# Sheet1.net
KiCad netlist of a schematic drawn in Altium Designer
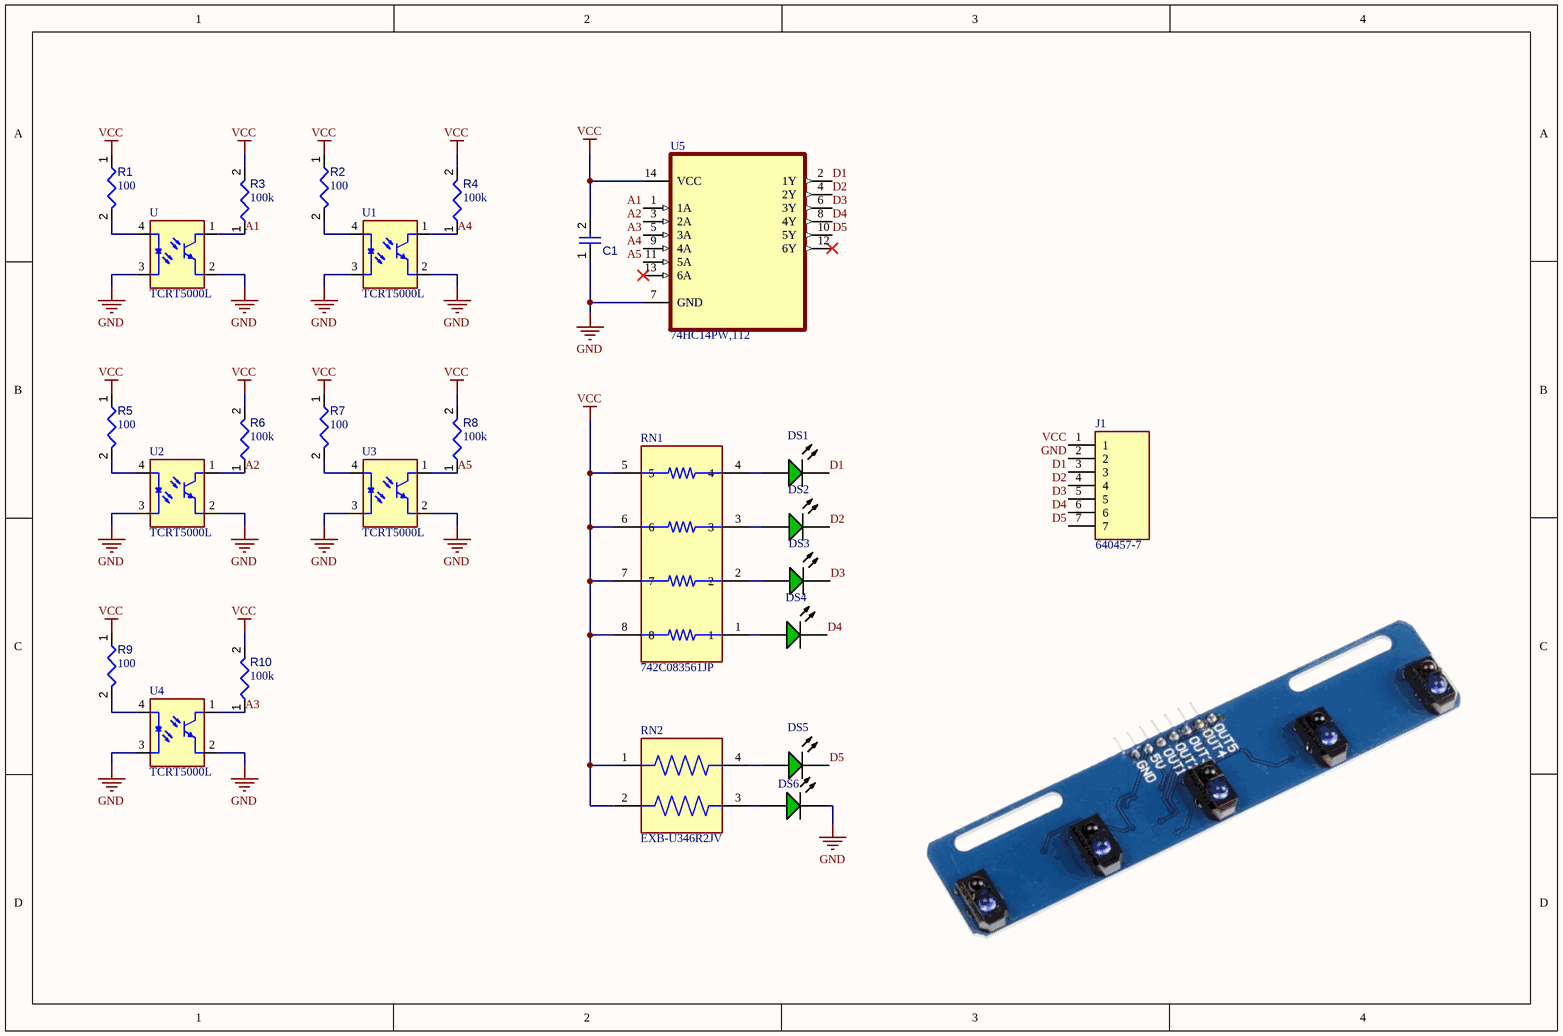
[diagram p0: Sheet1.SchDoc]

(export (version "E")
  (design (tool "Eeschema 10.0.6"))
  (components
    (comp (ref "C1")
      (value "Capacitor 1 uF +/- 10% 25 V 0805")
      (footprint "CAPC2013X145X50ML20T25")
      (description "Chip Capacitor, 1 uF, +/-10%, 25 V, 0805 (2012 Metric)")
      (fields (field (name "TOLERANCE") "10%"))
      (libsource (lib "Med khalil khlifi") (part "CAP-NP-2"))
    )
    (comp (ref "DS1")
      (value "HSMG-C190")
      (footprint "AVAG-HSMX-C190_V")
      (description "LED Uni-Color Green, 52 mW, 20 mA, -40 to 85 degC, 2-Pin SMD, RoHS, Tape and Reel")
      (fields (field (name "POWER") "52mW") (field (name "MANUFACTURER") "Avago"))
      (libsource (lib "Med khalil khlifi") (part "LED-GREEN-AK-2"))
    )
    (comp (ref "DS2")
      (value "HSMG-C190")
      (footprint "AVAG-HSMX-C190_V")
      (description "LED Uni-Color Green, 52 mW, 20 mA, -40 to 85 degC, 2-Pin SMD, RoHS, Tape and Reel")
      (fields (field (name "POWER") "52mW") (field (name "MANUFACTURER") "Avago"))
      (libsource (lib "Med khalil khlifi") (part "LED-GREEN-AK-2"))
    )
    (comp (ref "DS3")
      (value "HSMG-C190")
      (footprint "AVAG-HSMX-C190_V")
      (description "LED Uni-Color Green, 52 mW, 20 mA, -40 to 85 degC, 2-Pin SMD, RoHS, Tape and Reel")
      (fields (field (name "POWER") "52mW") (field (name "MANUFACTURER") "Avago"))
      (libsource (lib "Med khalil khlifi") (part "LED-GREEN-AK-2"))
    )
    (comp (ref "DS4")
      (value "HSMG-C190")
      (footprint "AVAG-HSMX-C190_V")
      (description "LED Uni-Color Green, 52 mW, 20 mA, -40 to 85 degC, 2-Pin SMD, RoHS, Tape and Reel")
      (fields (field (name "POWER") "52mW") (field (name "MANUFACTURER") "Avago"))
      (libsource (lib "Med khalil khlifi") (part "LED-GREEN-AK-2"))
    )
    (comp (ref "DS5")
      (value "HSMG-C190")
      (footprint "AVAG-HSMX-C190_V")
      (description "LED Uni-Color Green, 52 mW, 20 mA, -40 to 85 degC, 2-Pin SMD, RoHS, Tape and Reel")
      (fields (field (name "POWER") "52mW") (field (name "MANUFACTURER") "Avago"))
      (libsource (lib "Med khalil khlifi") (part "LED-GREEN-AK-2"))
    )
    (comp (ref "DS6")
      (value "HSMG-C190")
      (footprint "AVAG-HSMX-C190_V")
      (description "LED Uni-Color Green, 52 mW, 20 mA, -40 to 85 degC, 2-Pin SMD, RoHS, Tape and Reel")
      (fields (field (name "POWER") "52mW") (field (name "MANUFACTURER") "Avago"))
      (libsource (lib "Med khalil khlifi") (part "LED-GREEN-AK-2"))
    )
    (comp (ref "J1")
      (value "640457-7")
      (footprint "TE_640457-7")
      (description "07P MTA100 HDR ASSY SQ R/A F/L")
      (fields (field (name "MF") "TE Connectivity"))
      (libsource (lib "Header 7") (part "640457-7"))
    )
    (comp (ref "R1")
      (value "100")
      (footprint "RESC0402(1005)_L")
      (description "Chip Resistor, 100 Ohms, +/-1 %, 63 mW, -55 to 155 degC, 0402")
      (fields (field (name "POWER") "63mW") (field (name "TOLERANCE") "1%"))
      (libsource (lib "Med khalil khlifi") (part "RES-2"))
    )
    (comp (ref "R2")
      (value "100")
      (footprint "RESC0402(1005)_L")
      (description "Chip Resistor, 100 Ohms, +/-1 %, 63 mW, -55 to 155 degC, 0402")
      (fields (field (name "POWER") "63mW") (field (name "TOLERANCE") "1%"))
      (libsource (lib "Med khalil khlifi") (part "RES-2"))
    )
    (comp (ref "R3")
      (value "100k")
      (footprint "RESC1005X40X25ML05T05")
      (description "Chip Resistor, 100 KOhm, +/- 1%, 0.063 W, -55 to 155 degC, 0402 (1005 Metric)")
      (fields (field (name "TOLERANCE") "1%") (field (name "POWER") "63mW"))
      (libsource (lib "Med khalil khlifi") (part "RES-2"))
    )
    (comp (ref "R4")
      (value "100k")
      (footprint "RESC1005X40X25ML05T05")
      (description "Chip Resistor, 100 KOhm, +/- 1%, 0.063 W, -55 to 155 degC, 0402 (1005 Metric)")
      (fields (field (name "TOLERANCE") "1%") (field (name "POWER") "63mW"))
      (libsource (lib "Med khalil khlifi") (part "RES-2"))
    )
    (comp (ref "R5")
      (value "100")
      (footprint "RESC0402(1005)_L")
      (description "Chip Resistor, 100 Ohms, +/-1 %, 63 mW, -55 to 155 degC, 0402")
      (fields (field (name "POWER") "63mW") (field (name "TOLERANCE") "1%"))
      (libsource (lib "Med khalil khlifi") (part "RES-2"))
    )
    (comp (ref "R6")
      (value "100k")
      (footprint "RESC1005X40X25ML05T05")
      (description "Chip Resistor, 100 KOhm, +/- 1%, 0.063 W, -55 to 155 degC, 0402 (1005 Metric)")
      (fields (field (name "TOLERANCE") "1%") (field (name "POWER") "63mW"))
      (libsource (lib "Med khalil khlifi") (part "RES-2"))
    )
    (comp (ref "R7")
      (value "100")
      (footprint "RESC0402(1005)_L")
      (description "Chip Resistor, 100 Ohms, +/-1 %, 63 mW, -55 to 155 degC, 0402")
      (fields (field (name "POWER") "63mW") (field (name "TOLERANCE") "1%"))
      (libsource (lib "Med khalil khlifi") (part "RES-2"))
    )
    (comp (ref "R8")
      (value "100k")
      (footprint "RESC1005X40X25ML05T05")
      (description "Chip Resistor, 100 KOhm, +/- 1%, 0.063 W, -55 to 155 degC, 0402 (1005 Metric)")
      (fields (field (name "TOLERANCE") "1%") (field (name "POWER") "63mW"))
      (libsource (lib "Med khalil khlifi") (part "RES-2"))
    )
    (comp (ref "R9")
      (value "100")
      (footprint "RESC0402(1005)_L")
      (description "Chip Resistor, 100 Ohms, +/-1 %, 63 mW, -55 to 155 degC, 0402")
      (fields (field (name "POWER") "63mW") (field (name "TOLERANCE") "1%"))
      (libsource (lib "Med khalil khlifi") (part "RES-2"))
    )
    (comp (ref "R10")
      (value "100k")
      (footprint "RESC1005X40X25ML05T05")
      (description "Chip Resistor, 100 KOhm, +/- 1%, 0.063 W, -55 to 155 degC, 0402 (1005 Metric)")
      (fields (field (name "TOLERANCE") "1%") (field (name "POWER") "63mW"))
      (libsource (lib "Med khalil khlifi") (part "RES-2"))
    )
    (comp (ref "RN1")
      (value "742C083561JP")
      (footprint "RESCAV80P320X160X70-8N")
      (fields (field (name "MF") "CTS Resistor"))
      (libsource (lib "Resistor Array 4") (part "742C083561JP"))
    )
    (comp (ref "RN2")
      (value "EXB-U346R2JV")
      (footprint "RESCAXE_EXB-U346R2JV")
      (fields (field (name "MF") "Panasonic"))
      (libsource (lib "Res Array 2") (part "EXB-U346R2JV"))
    )
    (comp (ref "U")
      (value "TCRT5000L")
      (footprint "XDCR_TCRT5000L")
      (description "Reflective Optical Sensor 0.591 _15mm_ PCB Mount")
      (fields (field (name "MF") "Vishay"))
      (libsource (lib "TCRT5000L") (part "TCRT5000L"))
    )
    (comp (ref "U1")
      (value "TCRT5000L")
      (footprint "XDCR_TCRT5000L")
      (description "Reflective Optical Sensor 0.591 _15mm_ PCB Mount")
      (fields (field (name "MF") "Vishay"))
      (libsource (lib "TCRT5000L") (part "TCRT5000L"))
    )
    (comp (ref "U2")
      (value "TCRT5000L")
      (footprint "XDCR_TCRT5000L")
      (description "Reflective Optical Sensor 0.591 _15mm_ PCB Mount")
      (fields (field (name "MF") "Vishay"))
      (libsource (lib "TCRT5000L") (part "TCRT5000L"))
    )
    (comp (ref "U3")
      (value "TCRT5000L")
      (footprint "XDCR_TCRT5000L")
      (description "Reflective Optical Sensor 0.591 _15mm_ PCB Mount")
      (fields (field (name "MF") "Vishay"))
      (libsource (lib "TCRT5000L") (part "TCRT5000L"))
    )
    (comp (ref "U4")
      (value "TCRT5000L")
      (footprint "XDCR_TCRT5000L")
      (description "Reflective Optical Sensor 0.591 _15mm_ PCB Mount")
      (fields (field (name "MF") "Vishay"))
      (libsource (lib "TCRT5000L") (part "TCRT5000L"))
    )
    (comp (ref "U5")
      (value "74HC14PW,112")
      (footprint "SOP65P640X110-14N")
      (description "Inverter IC 6 Channel Schmitt Trigger 14-TSSOP")
      (fields (field (name "MF") "Nexperia"))
      (libsource (lib "74HC14") (part "74HC14PW,112"))
    )
  )
  (nets
    (net (code "1") (name "/A1") (class "Default")
      (node (ref "R3") (pin "1") (pinfunction "1_1") (pintype "passive"))
      (node (ref "U") (pin "1") (pinfunction "CO_1") (pintype "passive"))
      (node (ref "U5") (pin "1") (pinfunction "1A_1") (pintype "input"))
    )
    (net (code "2") (name "/A2") (class "Default")
      (node (ref "R6") (pin "1") (pinfunction "1_1") (pintype "passive"))
      (node (ref "U2") (pin "1") (pinfunction "CO_1") (pintype "passive"))
      (node (ref "U5") (pin "3") (pinfunction "2A_3") (pintype "input"))
    )
    (net (code "3") (name "/A3") (class "Default")
      (node (ref "R10") (pin "1") (pinfunction "1_1") (pintype "passive"))
      (node (ref "U4") (pin "1") (pinfunction "CO_1") (pintype "passive"))
      (node (ref "U5") (pin "5") (pinfunction "3A_5") (pintype "input"))
    )
    (net (code "4") (name "/A4") (class "Default")
      (node (ref "R4") (pin "1") (pinfunction "1_1") (pintype "passive"))
      (node (ref "U1") (pin "1") (pinfunction "CO_1") (pintype "passive"))
      (node (ref "U5") (pin "9") (pinfunction "4A_9") (pintype "input"))
    )
    (net (code "5") (name "/A5") (class "Default")
      (node (ref "R8") (pin "1") (pinfunction "1_1") (pintype "passive"))
      (node (ref "U3") (pin "1") (pinfunction "CO_1") (pintype "passive"))
      (node (ref "U5") (pin "11") (pinfunction "5A_11") (pintype "input"))
    )
    (net (code "6") (name "/D1") (class "Default")
      (node (ref "DS1") (pin "2") (pinfunction "K_2") (pintype "passive"))
      (node (ref "J1") (pin "3") (pinfunction "3_3") (pintype "passive"))
      (node (ref "U5") (pin "2") (pinfunction "1Y_2") (pintype "output"))
    )
    (net (code "7") (name "/D2") (class "Default")
      (node (ref "DS2") (pin "2") (pinfunction "K_2") (pintype "passive"))
      (node (ref "J1") (pin "4") (pinfunction "4_4") (pintype "passive"))
      (node (ref "U5") (pin "4") (pinfunction "2Y_4") (pintype "output"))
    )
    (net (code "8") (name "/D3") (class "Default")
      (node (ref "DS3") (pin "2") (pinfunction "K_2") (pintype "passive"))
      (node (ref "J1") (pin "5") (pinfunction "5_5") (pintype "passive"))
      (node (ref "U5") (pin "6") (pinfunction "3Y_6") (pintype "output"))
    )
    (net (code "9") (name "/D4") (class "Default")
      (node (ref "DS4") (pin "2") (pinfunction "K_2") (pintype "passive"))
      (node (ref "J1") (pin "6") (pinfunction "6_6") (pintype "passive"))
      (node (ref "U5") (pin "8") (pinfunction "4Y_8") (pintype "output"))
    )
    (net (code "10") (name "/D5") (class "Default")
      (node (ref "DS5") (pin "2") (pinfunction "K_2") (pintype "passive"))
      (node (ref "J1") (pin "7") (pinfunction "7_7") (pintype "passive"))
      (node (ref "U5") (pin "10") (pinfunction "5Y_10") (pintype "output"))
    )
    (net (code "11") (name "GND") (class "Default")
      (node (ref "C1") (pin "1") (pinfunction "1_1") (pintype "passive"))
      (node (ref "DS6") (pin "2") (pinfunction "K_2") (pintype "passive"))
      (node (ref "J1") (pin "2") (pinfunction "2_2") (pintype "passive"))
      (node (ref "U") (pin "2") (pinfunction "E_2") (pintype "passive"))
      (node (ref "U") (pin "3") (pinfunction "C_3") (pintype "passive"))
      (node (ref "U1") (pin "2") (pinfunction "E_2") (pintype "passive"))
      (node (ref "U1") (pin "3") (pinfunction "C_3") (pintype "passive"))
      (node (ref "U2") (pin "2") (pinfunction "E_2") (pintype "passive"))
      (node (ref "U2") (pin "3") (pinfunction "C_3") (pintype "passive"))
      (node (ref "U3") (pin "2") (pinfunction "E_2") (pintype "passive"))
      (node (ref "U3") (pin "3") (pinfunction "C_3") (pintype "passive"))
      (node (ref "U4") (pin "2") (pinfunction "E_2") (pintype "passive"))
      (node (ref "U4") (pin "3") (pinfunction "C_3") (pintype "passive"))
      (node (ref "U5") (pin "7") (pinfunction "GND_7") (pintype "passive"))
    )
    (net (code "12") (name "Net-(DS1-A)") (class "Default")
      (node (ref "DS1") (pin "1") (pinfunction "A_1") (pintype "passive"))
      (node (ref "RN1") (pin "4") (pinfunction "4_4") (pintype "passive"))
    )
    (net (code "13") (name "Net-(DS2-A)") (class "Default")
      (node (ref "DS2") (pin "1") (pinfunction "A_1") (pintype "passive"))
      (node (ref "RN1") (pin "3") (pinfunction "3_3") (pintype "passive"))
    )
    (net (code "14") (name "Net-(DS3-A)") (class "Default")
      (node (ref "DS3") (pin "1") (pinfunction "A_1") (pintype "passive"))
      (node (ref "RN1") (pin "2") (pinfunction "2_2") (pintype "passive"))
    )
    (net (code "15") (name "Net-(DS4-A)") (class "Default")
      (node (ref "DS4") (pin "1") (pinfunction "A_1") (pintype "passive"))
      (node (ref "RN1") (pin "1") (pinfunction "1_1") (pintype "passive"))
    )
    (net (code "16") (name "Net-(DS5-A)") (class "Default")
      (node (ref "DS5") (pin "1") (pinfunction "A_1") (pintype "passive"))
      (node (ref "RN2") (pin "4") (pinfunction "4_4") (pintype "passive"))
    )
    (net (code "17") (name "Net-(DS6-A)") (class "Default")
      (node (ref "DS6") (pin "1") (pinfunction "A_1") (pintype "passive"))
      (node (ref "RN2") (pin "3") (pinfunction "3_3") (pintype "passive"))
    )
    (net (code "18") (name "Net-(U-A)") (class "Default")
      (node (ref "R1") (pin "2") (pinfunction "2_2") (pintype "passive"))
      (node (ref "U") (pin "4") (pinfunction "A_4") (pintype "passive"))
    )
    (net (code "19") (name "Net-(U1-A)") (class "Default")
      (node (ref "R2") (pin "2") (pinfunction "2_2") (pintype "passive"))
      (node (ref "U1") (pin "4") (pinfunction "A_4") (pintype "passive"))
    )
    (net (code "20") (name "Net-(U2-A)") (class "Default")
      (node (ref "R5") (pin "2") (pinfunction "2_2") (pintype "passive"))
      (node (ref "U2") (pin "4") (pinfunction "A_4") (pintype "passive"))
    )
    (net (code "21") (name "Net-(U3-A)") (class "Default")
      (node (ref "R7") (pin "2") (pinfunction "2_2") (pintype "passive"))
      (node (ref "U3") (pin "4") (pinfunction "A_4") (pintype "passive"))
    )
    (net (code "22") (name "Net-(U4-A)") (class "Default")
      (node (ref "R9") (pin "2") (pinfunction "2_2") (pintype "passive"))
      (node (ref "U4") (pin "4") (pinfunction "A_4") (pintype "passive"))
    )
    (net (code "23") (name "VCC") (class "Default")
      (node (ref "C1") (pin "2") (pinfunction "2_2") (pintype "passive"))
      (node (ref "J1") (pin "1") (pinfunction "1_1") (pintype "passive"))
      (node (ref "R1") (pin "1") (pinfunction "1_1") (pintype "passive"))
      (node (ref "R10") (pin "2") (pinfunction "2_2") (pintype "passive"))
      (node (ref "R2") (pin "1") (pinfunction "1_1") (pintype "passive"))
      (node (ref "R3") (pin "2") (pinfunction "2_2") (pintype "passive"))
      (node (ref "R4") (pin "2") (pinfunction "2_2") (pintype "passive"))
      (node (ref "R5") (pin "1") (pinfunction "1_1") (pintype "passive"))
      (node (ref "R6") (pin "2") (pinfunction "2_2") (pintype "passive"))
      (node (ref "R7") (pin "1") (pinfunction "1_1") (pintype "passive"))
      (node (ref "R8") (pin "2") (pinfunction "2_2") (pintype "passive"))
      (node (ref "R9") (pin "1") (pinfunction "1_1") (pintype "passive"))
      (node (ref "RN1") (pin "5") (pinfunction "5_5") (pintype "passive"))
      (node (ref "RN1") (pin "6") (pinfunction "6_6") (pintype "passive"))
      (node (ref "RN1") (pin "7") (pinfunction "7_7") (pintype "passive"))
      (node (ref "RN1") (pin "8") (pinfunction "8_8") (pintype "passive"))
      (node (ref "RN2") (pin "1") (pinfunction "1_1") (pintype "passive"))
      (node (ref "RN2") (pin "2") (pinfunction "2_2") (pintype "passive"))
      (node (ref "U5") (pin "14") (pinfunction "VCC_14") (pintype "power_in"))
    )
    (net (code "24") (name "unconnected-(U5-6A-Pad13)") (class "Default")
      (node (ref "U5") (pin "13") (pinfunction "6A_13") (pintype "input+no_connect"))
    )
    (net (code "25") (name "unconnected-(U5-6Y-Pad12)") (class "Default")
      (node (ref "U5") (pin "12") (pinfunction "6Y_12") (pintype "output+no_connect"))
    )
  )
)
